# MCU.net
KiCad netlist of a schematic drawn in Altium Designer
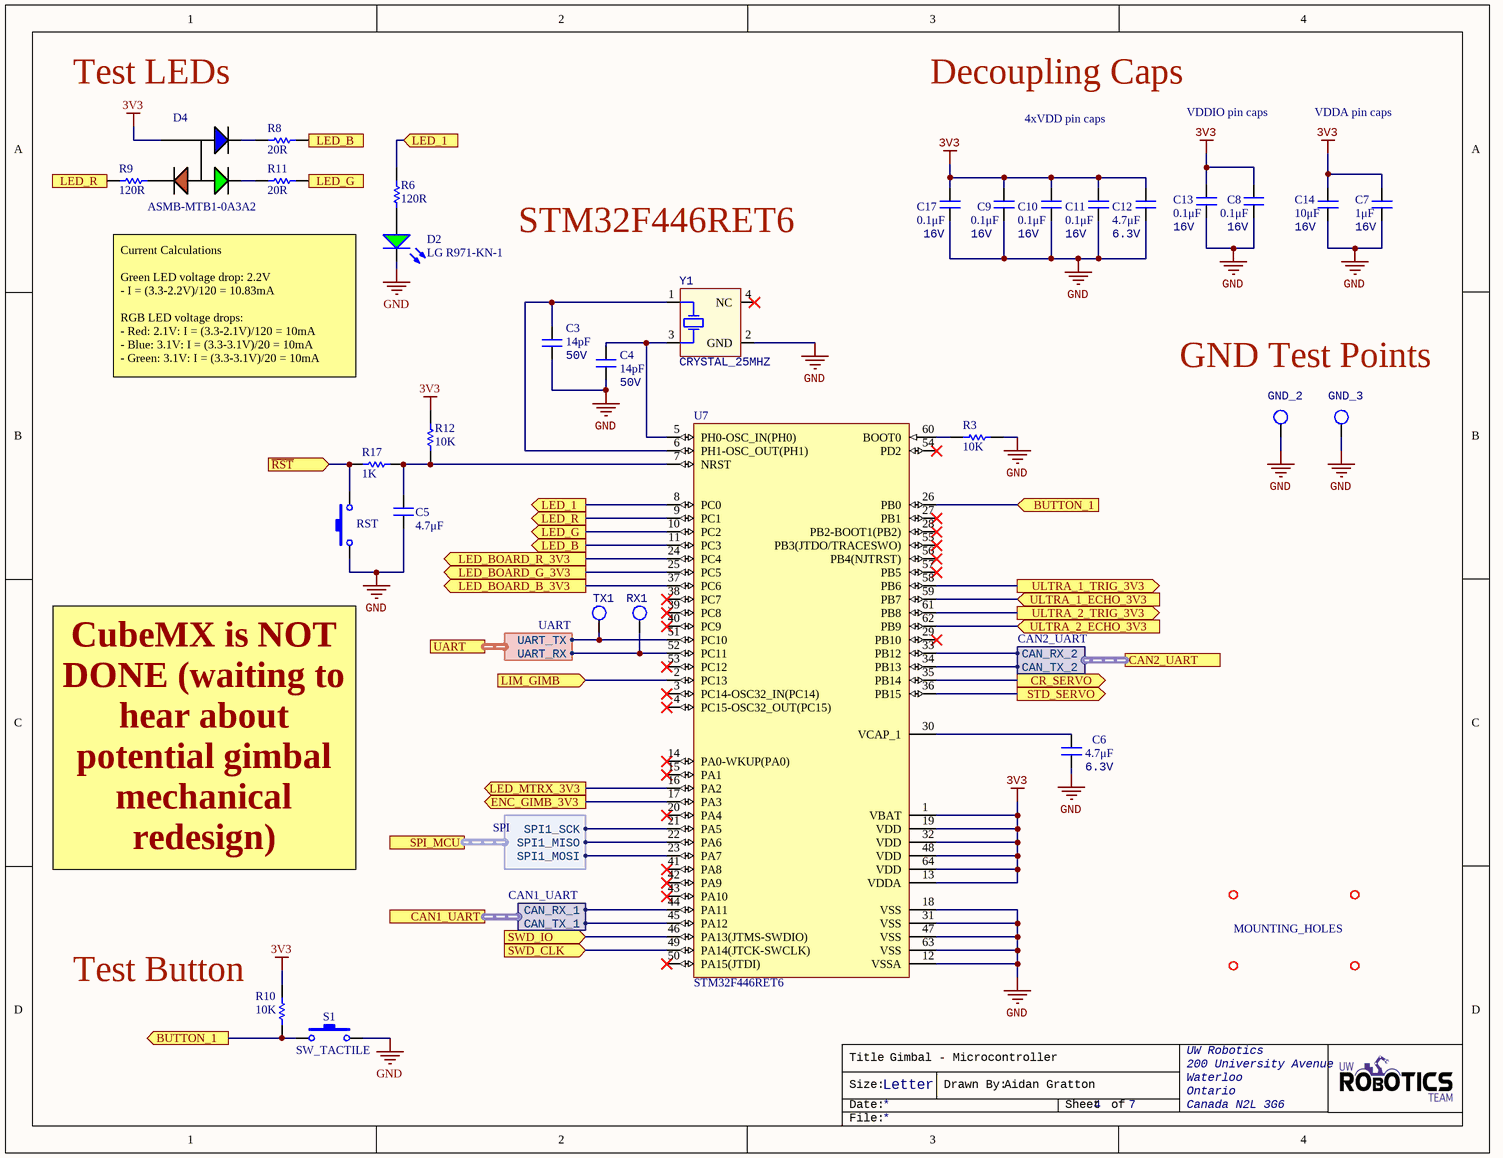
[diagram p0: MCU.SchDoc]

(export (version "E")
  (design (tool "Eeschema 10.0.6"))
  (components
    (comp (ref "C3")
      (value "14pF")
      (footprint "CAPC0603(1608)55_N")
      (description "Cap Ceramic 14pF 50V C0G 5% SMD 0603 125C Cardboard T/R")
      (fields
        (field (name "TOLERANCE") "5%")
        (field (name "VOLTAGE RATING (DC)") "50V")
        (field (name "Comment") "CL10C140JB8NNNC")
      )
      (libsource (lib "UWRT_Schematic_Library_2020") (part "CL10C140JB8NNNC"))
    )
    (comp (ref "C4")
      (value "14pF")
      (footprint "CAPC0603(1608)55_N")
      (description "Cap Ceramic 14pF 50V C0G 5% SMD 0603 125C Cardboard T/R")
      (fields
        (field (name "TOLERANCE") "5%")
        (field (name "VOLTAGE RATING (DC)") "50V")
        (field (name "Comment") "CL10C140JB8NNNC")
      )
      (libsource (lib "UWRT_Schematic_Library_2020") (part "CL10C140JB8NNNC"))
    )
    (comp (ref "C5")
      (value "4.7μF")
      (footprint "CAPC0603(1608)55_N")
      (description "CAP CER 4.7UF 6.3V X5R 0603")
      (fields (field (name "Comment") "CAP_4.7uF_0603"))
      (libsource (lib "UWRT_Schematic_Library_2020") (part "CAP_4.7uF_0603"))
    )
    (comp (ref "C6")
      (value "4.7μF")
      (footprint "CAPC0603(1608)55_N")
      (description "CAP CER 4.7UF 6.3V X5R 0603")
      (fields (field (name "VOLTAGE RATING") "6.3V") (field (name "Comment") "CAP_4.7uF_0603"))
      (libsource (lib "UWRT_Schematic_Library_2020") (part "CAP_4.7uF_0603"))
    )
    (comp (ref "C7")
      (value "1μF")
      (footprint "CAPC0603(1608)55_N")
      (description "CAP CER 1UF 16V Y5V 0603")
      (fields
        (field (name "VOLTAGE RATING") "16V")
        (field (name "MANUFACTURER PART NUMBER") "CC0603ZRY5V7BB105")
        (field (name "Comment") "CAP_1uF_16V_0603")
      )
      (libsource (lib "UWRT_Schematic_Library_2020") (part "CAP_1uF_16V_0603"))
    )
    (comp (ref "C8")
      (value "0.1μF")
      (footprint "CAPC0603(1608)55_N")
      (description "CAP CER 0.1UF 16V X7R 0603")
      (fields (field (name "VOLTAGE RATING") "16V") (field (name "Comment") "CAP_0.1uF_16V_0603"))
      (libsource (lib "UWRT_Schematic_Library_2020") (part "CAP_0.1uF_16V_0603"))
    )
    (comp (ref "C9")
      (value "0.1μF")
      (footprint "CAPC0603(1608)55_N")
      (description "CAP CER 0.1UF 16V X7R 0603")
      (fields (field (name "VOLTAGE RATING") "16V") (field (name "Comment") "CAP_0.1uF_16V_0603"))
      (libsource (lib "UWRT_Schematic_Library_2020") (part "CAP_0.1uF_16V_0603"))
    )
    (comp (ref "C10")
      (value "0.1μF")
      (footprint "CAPC0603(1608)55_N")
      (description "CAP CER 0.1UF 16V X7R 0603")
      (fields (field (name "VOLTAGE RATING") "16V") (field (name "Comment") "CAP_0.1uF_16V_0603"))
      (libsource (lib "UWRT_Schematic_Library_2020") (part "CAP_0.1uF_16V_0603"))
    )
    (comp (ref "C11")
      (value "0.1μF")
      (footprint "CAPC0603(1608)55_N")
      (description "CAP CER 0.1UF 16V X7R 0603")
      (fields (field (name "VOLTAGE RATING") "16V") (field (name "Comment") "CAP_0.1uF_16V_0603"))
      (libsource (lib "UWRT_Schematic_Library_2020") (part "CAP_0.1uF_16V_0603"))
    )
    (comp (ref "C12")
      (value "4.7μF")
      (footprint "CAPC0603(1608)55_N")
      (description "CAP CER 4.7UF 6.3V X5R 0603")
      (fields (field (name "VOLTAGE RATING") "6.3V") (field (name "Comment") "CAP_4.7uF_0603"))
      (libsource (lib "UWRT_Schematic_Library_2020") (part "CAP_4.7uF_0603"))
    )
    (comp (ref "C13")
      (value "0.1μF")
      (footprint "CAPC0603(1608)55_N")
      (description "CAP CER 0.1UF 16V X7R 0603")
      (fields (field (name "VOLTAGE RATING") "16V") (field (name "Comment") "CAP_0.1uF_16V_0603"))
      (libsource (lib "UWRT_Schematic_Library_2020") (part "CAP_0.1uF_16V_0603"))
    )
    (comp (ref "C14")
      (value "10μF")
      (footprint "CAPC0603(1608)55_N")
      (description "CAP CER 10000PF 16V X7R 0603")
      (fields (field (name "VOLTAGE RATING") "16V") (field (name "Comment") "CAP_10nF_0603"))
      (libsource (lib "UWRT_Schematic_Library_2020") (part "CAP_10nF_0603"))
    )
    (comp (ref "C17")
      (value "0.1μF")
      (footprint "CAPC0603(1608)55_N")
      (description "CAP CER 0.1UF 16V X7R 0603")
      (fields (field (name "VOLTAGE RATING") "16V") (field (name "Comment") "CAP_0.1uF_16V_0603"))
      (libsource (lib "UWRT_Schematic_Library_2020") (part "CAP_0.1uF_16V_0603"))
    )
    (comp (ref "D2")
      (value "LG R971-KN-1")
      (footprint "LED_0805_LINE")
      (description "LED GREEN DIFFUSED 0805 SMD")
      (libsource (lib "UWRT_Schematic_Library_2020") (part "DIO_LED_G"))
    )
    (comp (ref "D4")
      (value "LED_RGB")
      (footprint "LED_RGB")
      (description "LED RGB DIFFUSED 4PLCC SMD")
      (fields (field (name "MANUFACTURER PART NUMBER 1") "ASMB-MTB1-0A3A2"))
      (libsource (lib "UWRT_Schematic_Library_2020") (part "LED_RGB"))
    )
    (comp (ref "GND_2")
      (value "TESTPOINT_LOOP")
      (footprint "TESTPOINT_LOOP")
      (description "Loop testpoint through-hole pad")
      (libsource (lib "UWRT_Schematic_Library_2020") (part "TESTPOINT_LOOP"))
    )
    (comp (ref "GND_3")
      (value "TESTPOINT_LOOP")
      (footprint "TESTPOINT_LOOP")
      (description "Loop testpoint through-hole pad")
      (libsource (lib "UWRT_Schematic_Library_2020") (part "TESTPOINT_LOOP"))
    )
    (comp (ref "MH1")
      (value "MOUNTING_HOLES")
      (footprint "MOUNTING_HOLE")
      (description "6cm x 6cm")
      (libsource (lib "UWRT_Schematic_Library_2020") (part "MOUNTING_HOLES"))
    )
    (comp (ref "MH2")
      (value "MOUNTING_HOLES")
      (footprint "MOUNTING_HOLE")
      (description "6cm x 6cm")
      (libsource (lib "UWRT_Schematic_Library_2020") (part "MOUNTING_HOLES"))
    )
    (comp (ref "MH3")
      (value "MOUNTING_HOLES")
      (footprint "MOUNTING_HOLE")
      (description "6cm x 6cm")
      (libsource (lib "UWRT_Schematic_Library_2020") (part "MOUNTING_HOLES"))
    )
    (comp (ref "MH4")
      (value "MOUNTING_HOLES")
      (footprint "MOUNTING_HOLE")
      (description "6cm x 6cm")
      (libsource (lib "UWRT_Schematic_Library_2020") (part "MOUNTING_HOLES"))
    )
    (comp (ref "R3")
      (value "10K")
      (footprint "RESC0603(1608)_N")
      (description "RES SMD 10K OHM 5% 1/10W 0603")
      (fields (field (name "MANUFACTURER") "Yageo") (field (name "MPN") "RC0603JR-0710KL"))
      (libsource (lib "UWRT_Schematic_Library_2020") (part "RES_10K_0603"))
    )
    (comp (ref "R6")
      (value "120R")
      (footprint "RESC0603(1608)_N")
      (description "RES SMD 120 OHM 5% 1/10W 0603")
      (fields (field (name "MANUFACTURER") "Yageo") (field (name "MPN") "RC0603JR-07120RL"))
      (libsource (lib "UWRT_Schematic_Library_2020") (part "RES_120R_0603"))
    )
    (comp (ref "R8")
      (value "20R")
      (footprint "RESC0603(1608)_N")
      (description "RES SMD 20 OHM 5% 1/10W 0603")
      (fields (field (name "MANUFACTURER") "Yageo") (field (name "MPN") "RC0603JR-0720RL"))
      (libsource (lib "UWRT_Schematic_Library_2020") (part "RES_20R_0603"))
    )
    (comp (ref "R9")
      (value "120R")
      (footprint "RESC0603(1608)_N")
      (description "RES SMD 120 OHM 5% 1/10W 0603")
      (fields (field (name "MANUFACTURER") "Yageo") (field (name "MPN") "RC0603JR-07120RL"))
      (libsource (lib "UWRT_Schematic_Library_2020") (part "RES_120R_0603"))
    )
    (comp (ref "R10")
      (value "10K")
      (footprint "RESC0603(1608)_N")
      (description "RES SMD 10K OHM 5% 1/10W 0603")
      (fields (field (name "MANUFACTURER") "Yageo") (field (name "TOLERANCE") "5%"))
      (libsource (lib "UWRT_Schematic_Library_2020") (part "RES_10K_0603"))
    )
    (comp (ref "R11")
      (value "20R")
      (footprint "RESC0603(1608)_N")
      (description "RES SMD 20 OHM 5% 1/10W 0603")
      (fields (field (name "MANUFACTURER") "Yageo") (field (name "MPN") "RC0603JR-0720RL"))
      (libsource (lib "UWRT_Schematic_Library_2020") (part "RES_20R_0603"))
    )
    (comp (ref "R12")
      (value "10K")
      (footprint "RESC0603(1608)_N")
      (description "RES SMD 10K OHM 5% 1/10W 0603")
      (fields (field (name "MANUFACTURER") "Yageo") (field (name "MPN") "RC0603JR-0710KL"))
      (libsource (lib "UWRT_Schematic_Library_2020") (part "RES_10K_0603"))
    )
    (comp (ref "R17")
      (value "1K")
      (footprint "RESC0603(1608)_N")
      (description "RES SMD 1K OHM 5% 1/10W 0603")
      (fields (field (name "TOLERANCE") "5%") (field (name "Comment") "RES_1K_0603"))
      (libsource (lib "UWRT_Schematic_Library_2020") (part "RES_1K_0603"))
    )
    (comp (ref "RST")
      (value "SW_PWR")
      (footprint "PTS830GM140")
      (description "Power Switch (Red)")
      (libsource (lib "UWRT_Schematic_Library_2020") (part "SW_PWR"))
    )
    (comp (ref "RX1")
      (value "TESTPOINT_LOOP")
      (footprint "TESTPOINT_LOOP")
      (description "Loop testpoint through-hole pad")
      (libsource (lib "UWRT_Schematic_Library_2020") (part "TESTPOINT_LOOP"))
    )
    (comp (ref "S1")
      (value "SW_TACTILE")
      (footprint "B3U-1000P")
      (description "Tactile Switch (Grey)")
      (libsource (lib "UWRT_Schematic_Library_2020") (part "SW_TACTILE"))
    )
    (comp (ref "TX1")
      (value "TESTPOINT_LOOP")
      (footprint "TESTPOINT_LOOP")
      (description "Loop testpoint through-hole pad")
      (libsource (lib "UWRT_Schematic_Library_2020") (part "TESTPOINT_LOOP"))
    )
    (comp (ref "U7")
      (value "STM32F446RET6")
      (footprint "STM-LQFP64_L")
      (libsource (lib "UWRT_Schematic_Library_2020") (part "MCU_STM32F446RET6"))
    )
    (comp (ref "Y1")
      (value "CRYSTAL_25MHZ")
      (footprint "SOIC254P1016X440-4N")
      (description "CRYSTAL 25.0000MHZ 12PF SMD")
      (libsource (lib "UWRT_Schematic_Library_2020") (part "CRYSTAL_25MHZ"))
    )
  )
  (nets
    (net (code "5") (name "/BUTTON_1") (class "Default")
      (node (ref "R10") (pin "2") (pinfunction "2_2") (pintype "passive"))
      (node (ref "S1") (pin "1") (pinfunction "1_1") (pintype "passive"))
      (node (ref "U7") (pin "26") (pinfunction "PB0_26") (pintype "bidirectional"))
    )
    (net (code "6") (name "/CAN_RX_1") (class "Default")
      (node (ref "U7") (pin "44") (pinfunction "PA11_44") (pintype "bidirectional"))
    )
    (net (code "7") (name "/CAN_RX_2") (class "Default")
      (node (ref "U7") (pin "33") (pinfunction "PB12_33") (pintype "bidirectional"))
    )
    (net (code "8") (name "/CAN_TX_1") (class "Default")
      (node (ref "U7") (pin "45") (pinfunction "PA12_45") (pintype "bidirectional"))
    )
    (net (code "9") (name "/CAN_TX_2") (class "Default")
      (node (ref "U7") (pin "34") (pinfunction "PB13_34") (pintype "bidirectional"))
    )
    (net (code "10") (name "/CR_SERVO") (class "Default")
      (node (ref "U7") (pin "35") (pinfunction "PB14_35") (pintype "bidirectional"))
    )
    (net (code "11") (name "/ENC_GIMB_3V3") (class "Default")
      (node (ref "U7") (pin "17") (pinfunction "PA3_17") (pintype "bidirectional"))
    )
    (net (code "12") (name "/LED_1") (class "Default")
      (node (ref "R6") (pin "1") (pinfunction "1_1") (pintype "passive"))
      (node (ref "U7") (pin "8") (pinfunction "PC0_8") (pintype "bidirectional"))
    )
    (net (code "13") (name "/LED_B") (class "Default")
      (node (ref "R8") (pin "2") (pinfunction "2_2") (pintype "passive"))
      (node (ref "U7") (pin "11") (pinfunction "PC3_11") (pintype "bidirectional"))
    )
    (net (code "14") (name "/LED_BOARD_B_3V3") (class "Default")
      (node (ref "U7") (pin "37") (pinfunction "PC6_37") (pintype "bidirectional"))
    )
    (net (code "15") (name "/LED_BOARD_G_3V3") (class "Default")
      (node (ref "U7") (pin "25") (pinfunction "PC5_25") (pintype "bidirectional"))
    )
    (net (code "16") (name "/LED_BOARD_R_3V3") (class "Default")
      (node (ref "U7") (pin "24") (pinfunction "PC4_24") (pintype "bidirectional"))
    )
    (net (code "17") (name "/LED_G") (class "Default")
      (node (ref "R11") (pin "2") (pinfunction "2_2") (pintype "passive"))
      (node (ref "U7") (pin "10") (pinfunction "PC2_10") (pintype "bidirectional"))
    )
    (net (code "18") (name "/LED_MTRX_3V3") (class "Default")
      (node (ref "U7") (pin "16") (pinfunction "PA2_16") (pintype "bidirectional"))
    )
    (net (code "19") (name "/LED_R") (class "Default")
      (node (ref "R9") (pin "1") (pinfunction "1_1") (pintype "passive"))
      (node (ref "U7") (pin "9") (pinfunction "PC1_9") (pintype "bidirectional"))
    )
    (net (code "20") (name "/LIM_GIMB") (class "Default")
      (node (ref "U7") (pin "2") (pinfunction "PC13_2") (pintype "bidirectional"))
    )
    (net (code "21") (name "/SPI1_MISO") (class "Default")
      (node (ref "U7") (pin "22") (pinfunction "PA6_22") (pintype "bidirectional"))
    )
    (net (code "22") (name "/SPI1_MOSI") (class "Default")
      (node (ref "U7") (pin "23") (pinfunction "PA7_23") (pintype "bidirectional"))
    )
    (net (code "23") (name "/SPI1_SCK") (class "Default")
      (node (ref "U7") (pin "21") (pinfunction "PA5_21") (pintype "bidirectional"))
    )
    (net (code "24") (name "/STD_SERVO") (class "Default")
      (node (ref "U7") (pin "36") (pinfunction "PB15_36") (pintype "bidirectional"))
    )
    (net (code "25") (name "/SWD_CLK") (class "Default")
      (node (ref "U7") (pin "49") (pinfunction "PA14(JTCK-SWCLK)_49") (pintype "bidirectional"))
    )
    (net (code "26") (name "/SWD_IO") (class "Default")
      (node (ref "U7") (pin "46") (pinfunction "PA13(JTMS-SWDIO)_46") (pintype "bidirectional"))
    )
    (net (code "27") (name "/UART_RX") (class "Default")
      (node (ref "RX1") (pin "1") (pintype "passive"))
      (node (ref "U7") (pin "52") (pinfunction "PC11_52") (pintype "bidirectional"))
    )
    (net (code "28") (name "/UART_TX") (class "Default")
      (node (ref "TX1") (pin "1") (pintype "passive"))
      (node (ref "U7") (pin "51") (pinfunction "PC10_51") (pintype "bidirectional"))
    )
    (net (code "29") (name "/ULTRA_1_ECHO_3V3") (class "Default")
      (node (ref "U7") (pin "59") (pinfunction "PB7_59") (pintype "bidirectional"))
    )
    (net (code "30") (name "/ULTRA_1_TRIG_3V3") (class "Default")
      (node (ref "U7") (pin "58") (pinfunction "PB6_58") (pintype "bidirectional"))
    )
    (net (code "31") (name "/ULTRA_2_ECHO_3V3") (class "Default")
      (node (ref "U7") (pin "62") (pinfunction "PB9_62") (pintype "bidirectional"))
    )
    (net (code "32") (name "/ULTRA_2_TRIG_3V3") (class "Default")
      (node (ref "U7") (pin "61") (pinfunction "PB8_61") (pintype "bidirectional"))
    )
    (net (code "37") (name "/~{RST}") (class "Default")
      (node (ref "R17") (pin "1") (pinfunction "1_1") (pintype "passive"))
      (node (ref "RST") (pin "2") (pinfunction "2_2") (pintype "passive"))
    )
    (net (code "38") (name "3V3") (class "Default")
      (node (ref "C10") (pin "2") (pinfunction "2_2") (pintype "passive"))
      (node (ref "C11") (pin "2") (pinfunction "2_2") (pintype "passive"))
      (node (ref "C12") (pin "2") (pinfunction "2_2") (pintype "passive"))
      (node (ref "C13") (pin "2") (pinfunction "2_2") (pintype "passive"))
      (node (ref "C14") (pin "2") (pinfunction "2_2") (pintype "passive"))
      (node (ref "C17") (pin "2") (pinfunction "2_2") (pintype "passive"))
      (node (ref "C7") (pin "2") (pinfunction "2_2") (pintype "passive"))
      (node (ref "C8") (pin "2") (pinfunction "2_2") (pintype "passive"))
      (node (ref "C9") (pin "2") (pinfunction "2_2") (pintype "passive"))
      (node (ref "D4") (pin "4") (pinfunction "9_4") (pintype "passive"))
      (node (ref "R10") (pin "1") (pinfunction "1_1") (pintype "passive"))
      (node (ref "R12") (pin "2") (pinfunction "2_2") (pintype "passive"))
      (node (ref "U7") (pin "1") (pinfunction "VBAT_1") (pintype "power_in"))
      (node (ref "U7") (pin "13") (pinfunction "VDDA_13") (pintype "power_in"))
      (node (ref "U7") (pin "19") (pinfunction "VDD_19") (pintype "power_in"))
      (node (ref "U7") (pin "32") (pinfunction "VDD_32") (pintype "power_in"))
      (node (ref "U7") (pin "48") (pinfunction "VDD_48") (pintype "power_in"))
      (node (ref "U7") (pin "64") (pinfunction "VDD_64") (pintype "power_in"))
    )
    (net (code "39") (name "GND") (class "Default")
      (node (ref "C10") (pin "1") (pinfunction "1_1") (pintype "passive"))
      (node (ref "C11") (pin "1") (pinfunction "1_1") (pintype "passive"))
      (node (ref "C12") (pin "1") (pinfunction "1_1") (pintype "passive"))
      (node (ref "C13") (pin "1") (pinfunction "1_1") (pintype "passive"))
      (node (ref "C14") (pin "1") (pinfunction "1_1") (pintype "passive"))
      (node (ref "C17") (pin "1") (pinfunction "1_1") (pintype "passive"))
      (node (ref "C3") (pin "1") (pinfunction "1_1") (pintype "passive"))
      (node (ref "C4") (pin "1") (pinfunction "1_1") (pintype "passive"))
      (node (ref "C5") (pin "1") (pinfunction "1_1") (pintype "passive"))
      (node (ref "C6") (pin "1") (pinfunction "1_1") (pintype "passive"))
      (node (ref "C7") (pin "1") (pinfunction "1_1") (pintype "passive"))
      (node (ref "C8") (pin "1") (pinfunction "1_1") (pintype "passive"))
      (node (ref "C9") (pin "1") (pinfunction "1_1") (pintype "passive"))
      (node (ref "D2") (pin "2") (pinfunction "K_2") (pintype "passive"))
      (node (ref "GND_2") (pin "1") (pintype "passive"))
      (node (ref "GND_3") (pin "1") (pintype "passive"))
      (node (ref "R3") (pin "2") (pinfunction "2_2") (pintype "passive"))
      (node (ref "RST") (pin "1") (pinfunction "1_1") (pintype "passive"))
      (node (ref "S1") (pin "2") (pinfunction "2_2") (pintype "passive"))
      (node (ref "U7") (pin "12") (pinfunction "VSSA_12") (pintype "power_in"))
      (node (ref "U7") (pin "18") (pinfunction "VSS_18") (pintype "power_in"))
      (node (ref "U7") (pin "31") (pinfunction "VSS_31") (pintype "power_in"))
      (node (ref "U7") (pin "47") (pinfunction "VSS_47") (pintype "power_in"))
      (node (ref "U7") (pin "63") (pinfunction "VSS_63") (pintype "power_in"))
      (node (ref "Y1") (pin "2") (pinfunction "GND_2") (pintype "power_in"))
    )
    (net (code "40") (name "Net-(D2-A)") (class "Default")
      (node (ref "D2") (pin "1") (pinfunction "A_1") (pintype "passive"))
      (node (ref "R6") (pin "2") (pinfunction "2_2") (pintype "passive"))
    )
    (net (code "41") (name "Net-(D4-10)") (class "Default")
      (node (ref "D4") (pin "3") (pinfunction "10_3") (pintype "passive"))
      (node (ref "R8") (pin "1") (pinfunction "1_1") (pintype "passive"))
    )
    (net (code "42") (name "Net-(D4-11)") (class "Default")
      (node (ref "D4") (pin "1") (pinfunction "11_1") (pintype "passive"))
      (node (ref "R9") (pin "2") (pinfunction "2_2") (pintype "passive"))
    )
    (net (code "43") (name "Net-(D4-12)") (class "Default")
      (node (ref "D4") (pin "2") (pinfunction "12_2") (pintype "passive"))
      (node (ref "R11") (pin "1") (pinfunction "1_1") (pintype "passive"))
    )
    (net (code "44") (name "Net-(U7-BOOT0)") (class "Default")
      (node (ref "R3") (pin "1") (pinfunction "1_1") (pintype "passive"))
      (node (ref "U7") (pin "60") (pinfunction "BOOT0_60") (pintype "input"))
    )
    (net (code "45") (name "Net-(U7-NRST)") (class "Default")
      (node (ref "C5") (pin "2") (pinfunction "2_2") (pintype "passive"))
      (node (ref "R12") (pin "1") (pinfunction "1_1") (pintype "passive"))
      (node (ref "R17") (pin "2") (pinfunction "2_2") (pintype "passive"))
      (node (ref "U7") (pin "7") (pinfunction "NRST_7") (pintype "bidirectional"))
    )
    (net (code "46") (name "Net-(U7-PH0-OSC_IN(PH0))") (class "Default")
      (node (ref "C4") (pin "2") (pinfunction "2_2") (pintype "passive"))
      (node (ref "U7") (pin "5") (pinfunction "PH0-OSC_IN(PH0)_5") (pintype "bidirectional"))
      (node (ref "Y1") (pin "3") (pinfunction "HOT_3") (pintype "passive"))
    )
    (net (code "47") (name "Net-(U7-PH1-OSC_OUT(PH1))") (class "Default")
      (node (ref "C3") (pin "2") (pinfunction "2_2") (pintype "passive"))
      (node (ref "U7") (pin "6") (pinfunction "PH1-OSC_OUT(PH1)_6") (pintype "bidirectional"))
      (node (ref "Y1") (pin "1") (pinfunction "HOT_1") (pintype "passive"))
    )
    (net (code "48") (name "Net-(U7-VCAP_1)") (class "Default")
      (node (ref "C6") (pin "2") (pinfunction "2_2") (pintype "passive"))
      (node (ref "U7") (pin "30") (pinfunction "VCAP_1_30") (pintype "passive"))
    )
    (net (code "49") (name "unconnected-(U7-PA0-WKUP(PA0)-Pad14)") (class "Default")
      (node (ref "U7") (pin "14") (pinfunction "PA0-WKUP(PA0)_14") (pintype "bidirectional+no_connect"))
    )
    (net (code "50") (name "unconnected-(U7-PA1-Pad15)") (class "Default")
      (node (ref "U7") (pin "15") (pinfunction "PA1_15") (pintype "bidirectional+no_connect"))
    )
    (net (code "51") (name "unconnected-(U7-PA4-Pad20)") (class "Default")
      (node (ref "U7") (pin "20") (pinfunction "PA4_20") (pintype "bidirectional+no_connect"))
    )
    (net (code "52") (name "unconnected-(U7-PA8-Pad41)") (class "Default")
      (node (ref "U7") (pin "41") (pinfunction "PA8_41") (pintype "bidirectional+no_connect"))
    )
    (net (code "53") (name "unconnected-(U7-PA9-Pad42)") (class "Default")
      (node (ref "U7") (pin "42") (pinfunction "PA9_42") (pintype "bidirectional+no_connect"))
    )
    (net (code "54") (name "unconnected-(U7-PA10-Pad43)") (class "Default")
      (node (ref "U7") (pin "43") (pinfunction "PA10_43") (pintype "bidirectional+no_connect"))
    )
    (net (code "55") (name "unconnected-(U7-PA15(JTDI)-Pad50)") (class "Default")
      (node (ref "U7") (pin "50") (pinfunction "PA15(JTDI)_50") (pintype "bidirectional+no_connect"))
    )
    (net (code "56") (name "unconnected-(U7-PB1-Pad27)") (class "Default")
      (node (ref "U7") (pin "27") (pinfunction "PB1_27") (pintype "bidirectional+no_connect"))
    )
    (net (code "57") (name "unconnected-(U7-PB2-BOOT1(PB2)-Pad28)") (class "Default")
      (node (ref "U7") (pin "28") (pinfunction "PB2-BOOT1(PB2)_28") (pintype "bidirectional+no_connect"))
    )
    (net (code "58") (name "unconnected-(U7-PB3(JTDO{slash}TRACESWO)-Pad55)") (class "Default")
      (node (ref "U7") (pin "55") (pinfunction "PB3(JTDO/TRACESWO)_55") (pintype "bidirectional+no_connect"))
    )
    (net (code "59") (name "unconnected-(U7-PB4(NJTRST)-Pad56)") (class "Default")
      (node (ref "U7") (pin "56") (pinfunction "PB4(NJTRST)_56") (pintype "bidirectional+no_connect"))
    )
    (net (code "60") (name "unconnected-(U7-PB5-Pad57)") (class "Default")
      (node (ref "U7") (pin "57") (pinfunction "PB5_57") (pintype "bidirectional+no_connect"))
    )
    (net (code "61") (name "unconnected-(U7-PB10-Pad29)") (class "Default")
      (node (ref "U7") (pin "29") (pinfunction "PB10_29") (pintype "bidirectional+no_connect"))
    )
    (net (code "62") (name "unconnected-(U7-PC7-Pad38)") (class "Default")
      (node (ref "U7") (pin "38") (pinfunction "PC7_38") (pintype "bidirectional+no_connect"))
    )
    (net (code "63") (name "unconnected-(U7-PC8-Pad39)") (class "Default")
      (node (ref "U7") (pin "39") (pinfunction "PC8_39") (pintype "bidirectional+no_connect"))
    )
    (net (code "64") (name "unconnected-(U7-PC9-Pad40)") (class "Default")
      (node (ref "U7") (pin "40") (pinfunction "PC9_40") (pintype "bidirectional+no_connect"))
    )
    (net (code "65") (name "unconnected-(U7-PC12-Pad53)") (class "Default")
      (node (ref "U7") (pin "53") (pinfunction "PC12_53") (pintype "bidirectional+no_connect"))
    )
    (net (code "66") (name "unconnected-(U7-PC14-OSC32_IN(PC14)-Pad3)") (class "Default")
      (node (ref "U7") (pin "3") (pinfunction "PC14-OSC32_IN(PC14)_3") (pintype "bidirectional+no_connect"))
    )
    (net (code "67") (name "unconnected-(U7-PC15-OSC32_OUT(PC15)-Pad4)") (class "Default")
      (node (ref "U7") (pin "4") (pinfunction "PC15-OSC32_OUT(PC15)_4") (pintype "bidirectional+no_connect"))
    )
    (net (code "68") (name "unconnected-(U7-PD2-Pad54)") (class "Default")
      (node (ref "U7") (pin "54") (pinfunction "PD2_54") (pintype "bidirectional+no_connect"))
    )
    (net (code "69") (name "unconnected-(Y1-NC-Pad4)") (class "Default")
      (node (ref "Y1") (pin "4") (pinfunction "NC_4") (pintype "passive+no_connect"))
    )
  )
)
